# qPCR_pcb_breakout_SN74LVC1G04DBVR.net
KiCad netlist of a schematic drawn in EAGLE
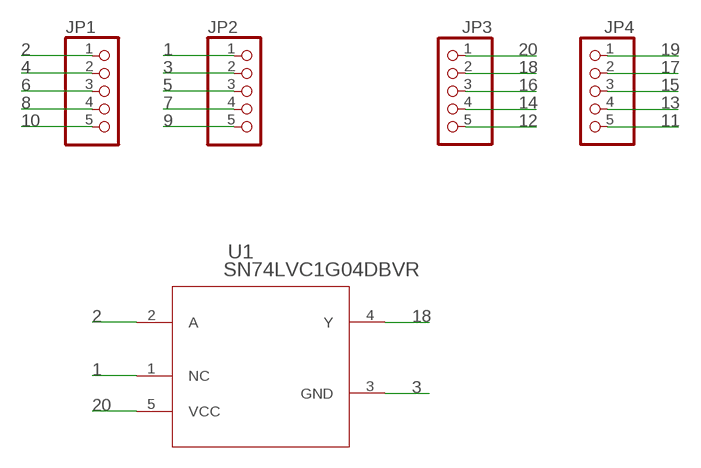
[diagram p0: schematic, sheet 1]

(export (version "E")
  (design (tool "Eeschema 10.0.6"))
  (components
    (comp (ref "JP1")
      (value "PINHD-1X5R")
      (footprint "eagle-import:1X05R")
      (libsource (lib "eagle-import") (part "PINHD-1X5R"))
    )
    (comp (ref "JP2")
      (value "PINHD-1X5R")
      (footprint "eagle-import:1X05R")
      (libsource (lib "eagle-import") (part "PINHD-1X5R"))
    )
    (comp (ref "JP3")
      (value "PINHD-1X5R")
      (footprint "eagle-import:1X05R")
      (libsource (lib "eagle-import") (part "PINHD-1X5R"))
    )
    (comp (ref "JP4")
      (value "PINHD-1X5R")
      (footprint "eagle-import:1X05R")
      (libsource (lib "eagle-import") (part "PINHD-1X5R"))
    )
    (comp (ref "U1")
      (value "SN74LVC1G04DBVR")
      (footprint "eagle-import:DBV5")
      (fields
        (field (name "GENERIC_PART_NUMBER") "SN74LVC1G04")
        (field (name "MANUFACTURER") "Texas Instruments")
      )
      (libsource (lib "eagle-import") (part "SN74LVC1G04DBVR"))
    )
  )
  (nets
    (net (code "1") (name "/1") (class "Default")
      (node (ref "JP2") (pin "1") (pinfunction "1_1") (pintype "passive"))
      (node (ref "U1") (pin "1") (pinfunction "NC_1") (pintype "passive"))
    )
    (net (code "2") (name "/2") (class "Default")
      (node (ref "JP1") (pin "1") (pinfunction "1_1") (pintype "passive"))
      (node (ref "U1") (pin "2") (pinfunction "A_2") (pintype "input"))
    )
    (net (code "3") (name "/3") (class "Default")
      (node (ref "JP2") (pin "2") (pinfunction "2_2") (pintype "passive"))
      (node (ref "U1") (pin "3") (pinfunction "GND_3") (pintype "power_in"))
    )
    (net (code "4") (name "/4") (class "Default")
      (node (ref "JP1") (pin "2") (pinfunction "2_2") (pintype "passive"))
    )
    (net (code "5") (name "/5") (class "Default")
      (node (ref "JP2") (pin "3") (pinfunction "3_3") (pintype "passive"))
    )
    (net (code "6") (name "/6") (class "Default")
      (node (ref "JP1") (pin "3") (pinfunction "3_3") (pintype "passive"))
    )
    (net (code "7") (name "/7") (class "Default")
      (node (ref "JP2") (pin "4") (pinfunction "4_4") (pintype "passive"))
    )
    (net (code "8") (name "/8") (class "Default")
      (node (ref "JP1") (pin "4") (pinfunction "4_4") (pintype "passive"))
    )
    (net (code "9") (name "/9") (class "Default")
      (node (ref "JP2") (pin "5") (pinfunction "5_5") (pintype "passive"))
    )
    (net (code "10") (name "/10") (class "Default")
      (node (ref "JP1") (pin "5") (pinfunction "5_5") (pintype "passive"))
    )
    (net (code "11") (name "/11") (class "Default")
      (node (ref "JP4") (pin "5") (pinfunction "5_5") (pintype "passive"))
    )
    (net (code "12") (name "/12") (class "Default")
      (node (ref "JP3") (pin "5") (pinfunction "5_5") (pintype "passive"))
    )
    (net (code "13") (name "/13") (class "Default")
      (node (ref "JP4") (pin "4") (pinfunction "4_4") (pintype "passive"))
    )
    (net (code "14") (name "/14") (class "Default")
      (node (ref "JP3") (pin "4") (pinfunction "4_4") (pintype "passive"))
    )
    (net (code "15") (name "/15") (class "Default")
      (node (ref "JP4") (pin "3") (pinfunction "3_3") (pintype "passive"))
    )
    (net (code "16") (name "/16") (class "Default")
      (node (ref "JP3") (pin "3") (pinfunction "3_3") (pintype "passive"))
    )
    (net (code "17") (name "/17") (class "Default")
      (node (ref "JP4") (pin "2") (pinfunction "2_2") (pintype "passive"))
    )
    (net (code "18") (name "/18") (class "Default")
      (node (ref "JP3") (pin "2") (pinfunction "2_2") (pintype "passive"))
      (node (ref "U1") (pin "4") (pinfunction "Y_4") (pintype "output"))
    )
    (net (code "19") (name "/19") (class "Default")
      (node (ref "JP4") (pin "1") (pinfunction "1_1") (pintype "passive"))
    )
    (net (code "20") (name "/20") (class "Default")
      (node (ref "JP3") (pin "1") (pinfunction "1_1") (pintype "passive"))
      (node (ref "U1") (pin "5") (pinfunction "VCC_5") (pintype "power_in"))
    )
  )
)
